# reefvolt_power_essentials_top.net
KiCad netlist of a schematic drawn in Altium Designer
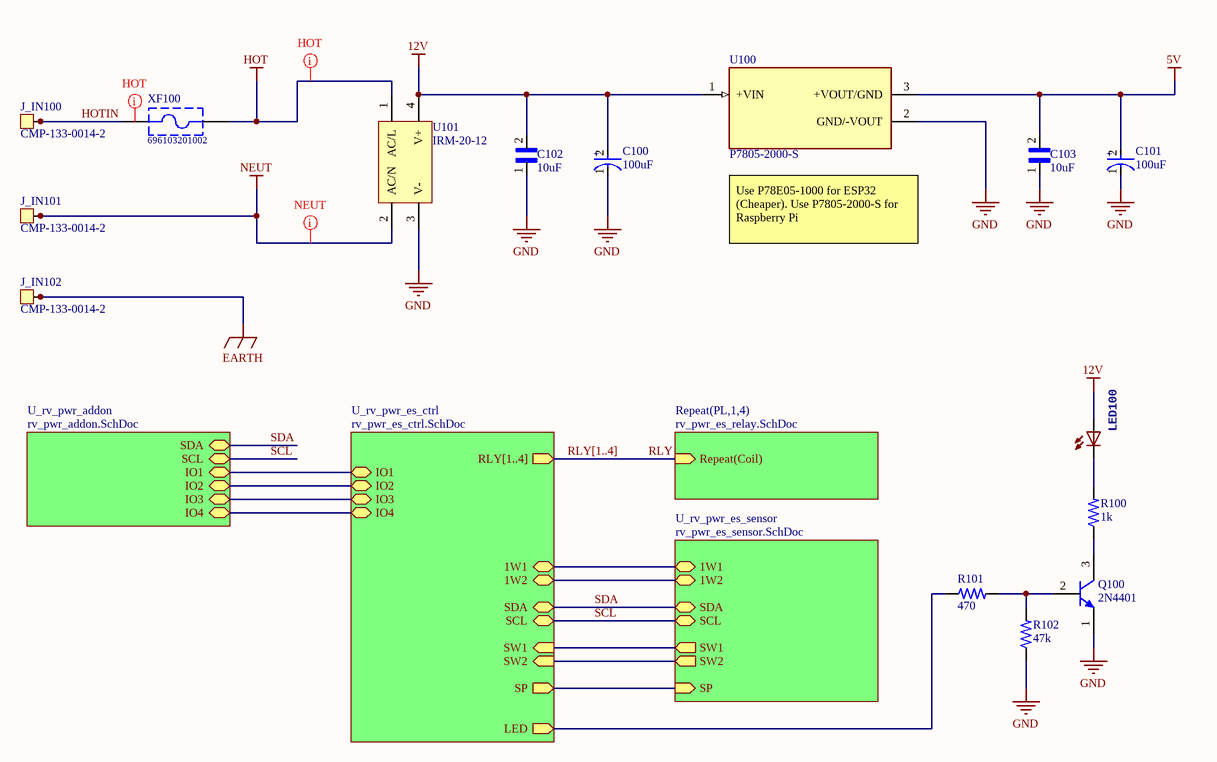
[diagram p0: reefvolt_power_essentials_top.SchDoc]

(export (version "E")
  (design (tool "Eeschema 10.0.6"))
  (components
    (comp (ref "C100")
      (value "100uF")
      (footprint "FP-RAD-TH-D_8_0_5-L_11_5-MFG")
      (description "Cap Aluminum 100uF 25V 20% (8 X 11.5mm) Radial 3.5mm 500mA 2000 hr 125°C Bulk")
      (fields (field (name "Comment") "CAP 100uF 25V Aluminum 8mm Through Hole"))
      (libsource (lib "StackFoundry LLC") (part "203bc49f2ac43e59fd269a8c329ed05"))
    )
    (comp (ref "C101")
      (value "100uF")
      (footprint "FP-RAD-TH-D_8_0_5-L_11_5-MFG")
      (description "Cap Aluminum 100uF 25V 20% (8 X 11.5mm) Radial 3.5mm 500mA 2000 hr 125°C Bulk")
      (fields (field (name "Comment") "CAP 100uF 25V Aluminum 8mm Through Hole"))
      (libsource (lib "StackFoundry LLC") (part "203bc49f2ac43e59fd269a8c329ed05"))
    )
    (comp (ref "C102")
      (value "10uF")
      (footprint "CAPRB250W50L550T350H600")
      (description "FG Series 10 uF 25 V ±10% Tolerance X7R Radial Multilayer Ceramic Capacitor")
      (fields (field (name "MF") "TDK") (field (name "DIGI-KEY_PART_NUMBER") "445-173156-1-ND"))
      (libsource (lib "StackFoundry LLC") (part "FG16X7R1E106KRT06"))
    )
    (comp (ref "C103")
      (value "10uF")
      (footprint "CAPRB250W50L550T350H600")
      (description "FG Series 10 uF 25 V ±10% Tolerance X7R Radial Multilayer Ceramic Capacitor")
      (fields (field (name "MF") "TDK") (field (name "DIGI-KEY_PART_NUMBER") "445-173156-1-ND"))
      (libsource (lib "StackFoundry LLC") (part "FG16X7R1E106KRT06"))
    )
    (comp (ref "J_IN100")
      (value "CMP-133-0014-2")
      (footprint "0197054203")
      (description "Molex  0197054203")
      (libsource (lib "StackFoundry LLC") (part "TAB_QUICKCON"))
    )
    (comp (ref "J_IN101")
      (value "CMP-133-0014-2")
      (footprint "0197054203")
      (description "Molex  0197054203")
      (libsource (lib "StackFoundry LLC") (part "TAB_QUICKCON"))
    )
    (comp (ref "J_IN102")
      (value "CMP-133-0014-2")
      (footprint "0197054203")
      (description "Molex  0197054203")
      (libsource (lib "StackFoundry LLC") (part "TAB_QUICKCON"))
    )
    (comp (ref "LED100") (value "~") (footprint "LED5MM") (libsource (lib "general") (part "LED5MM")))
    (comp (ref "Q100")
      (value "2N4401")
      (footprint "ONSC-TO-92-3-29-11")
      (description "Transistor NPN Silicon 40V IC=600ma TO-92 Case General Purpose Amplifier And Switch")
      (fields (field (name "MF") "Rectron"))
      (libsource (lib "StackFoundry LLC") (part "ONSC-NPN-E1B2C3-3"))
    )
    (comp (ref "R100")
      (value "1k")
      (footprint "0207/10")
      (description "Res Carbon Film 1K Ohm 5% 1/4W -500ppm/°C to 350ppm/°C Conformal AXL Thru-Hole Paper T/R")
      (fields (field (name "Comment") "1k TH 0207 5% 0.25W"))
      (libsource (lib "StackFoundry LLC") (part "R-US"))
    )
    (comp (ref "R101")
      (value "470")
      (footprint "0207/10")
      (description "Res Carbon Film 470 Ohm 5% 1/4W -500ppm/°C to 350ppm/°C Conformal AXL Thru-Hole Paper T/R")
      (fields (field (name "Comment") "470 TH 0207 5% 0.25W"))
      (libsource (lib "StackFoundry LLC") (part "R-US"))
    )
    (comp (ref "R102")
      (value "47k")
      (footprint "0207/10 - Cloned")
      (description "Res Carbon Film 47K Ohm 5% 1/4W -500ppm/°C to 350ppm/°C Conformal AXL Thru-Hole Paper T/R")
      (fields (field (name "Comment") "47k TH 0207 5% 1/4W"))
      (libsource (lib "StackFoundry LLC") (part "R-US"))
    )
    (comp (ref "U100")
      (value "P7805-2000-S")
      (footprint "CONV_P7805-2000")
      (description "Module DC-DC 24VIN 1-OUT 5V 2A 10W 3-Pin SIP Module Tube")
      (libsource (lib "StackFoundry LLC") (part "P7805-2000-S"))
    )
    (comp (ref "U101")
      (value "IRM-20-12")
      (footprint "MEANW-IRM-20-12")
      (description "Single Output Encapsulated Type, 12 V, 1.8 A, 21.6 W, -40 to 85 degC, 4-Pin THD, RoHS")
      (fields (field (name "MANUFACTURER") "Mean Well"))
      (libsource (lib "Altium Content Vault") (part "MEANW-IRM-20-12-4"))
    )
    (comp (ref "XF100")
      (value "696103201002")
      (footprint "696103201002")
      (description "WR-FSH Fuse Holder Blocks Fuse Holder Blocks Clip Cover for PCB - THR Version")
      (libsource (lib "StackFoundry LLC") (part "WE-FUSE-2"))
    )
  )
  (nets
    (net (code "7") (name "/HOTIN") (class "Default")
      (node (ref "J_IN100") (pin "1") (pinfunction "1_1") (pintype "passive"))
      (node (ref "J_IN100") (pin "2") (pinfunction "2_2") (pintype "passive"))
      (node (ref "J_IN100") (pin "3") (pinfunction "3_3") (pintype "passive"))
      (node (ref "XF100") (pin "1") (pinfunction "1_1") (pintype "passive"))
    )
    (net (code "12") (name "/LED") (class "Default")
      (node (ref "R101") (pin "1") (pinfunction "1_1") (pintype "passive"))
    )
    (net (code "20") (name "5V") (class "Default")
      (node (ref "C101") (pin "2") (pinfunction "A_2") (pintype "passive"))
      (node (ref "C103") (pin "2") (pinfunction "2_2") (pintype "passive"))
      (node (ref "U100") (pin "3") (pinfunction "+VOUT/GND_3") (pintype "power_in"))
    )
    (net (code "21") (name "12V") (class "Default")
      (node (ref "C100") (pin "2") (pinfunction "A_2") (pintype "passive"))
      (node (ref "C102") (pin "2") (pinfunction "2_2") (pintype "passive"))
      (node (ref "LED100") (pin "A") (pinfunction "A_A") (pintype "passive"))
      (node (ref "U100") (pin "1") (pinfunction "+VIN_1") (pintype "input"))
      (node (ref "U101") (pin "4") (pinfunction "V+_4") (pintype "power_in"))
    )
    (net (code "22") (name "EARTH") (class "Default")
      (node (ref "J_IN102") (pin "1") (pinfunction "1_1") (pintype "passive"))
      (node (ref "J_IN102") (pin "2") (pinfunction "2_2") (pintype "passive"))
      (node (ref "J_IN102") (pin "3") (pinfunction "3_3") (pintype "passive"))
    )
    (net (code "23") (name "GND") (class "Default")
      (node (ref "C100") (pin "1") (pinfunction "C_1") (pintype "passive"))
      (node (ref "C101") (pin "1") (pinfunction "C_1") (pintype "passive"))
      (node (ref "C102") (pin "1") (pinfunction "1_1") (pintype "passive"))
      (node (ref "C103") (pin "1") (pinfunction "1_1") (pintype "passive"))
      (node (ref "Q100") (pin "1") (pinfunction "E_1") (pintype "passive"))
      (node (ref "R102") (pin "1") (pinfunction "1_1") (pintype "passive"))
      (node (ref "U100") (pin "2") (pinfunction "GND/-VOUT_2") (pintype "power_in"))
      (node (ref "U101") (pin "3") (pinfunction "V-_3") (pintype "power_in"))
    )
    (net (code "24") (name "HOT") (class "Default")
      (node (ref "U101") (pin "1") (pinfunction "AC/L_1") (pintype "passive"))
      (node (ref "XF100") (pin "2") (pinfunction "2_2") (pintype "passive"))
    )
    (net (code "25") (name "NEUT") (class "Default")
      (node (ref "J_IN101") (pin "1") (pinfunction "1_1") (pintype "passive"))
      (node (ref "J_IN101") (pin "2") (pinfunction "2_2") (pintype "passive"))
      (node (ref "J_IN101") (pin "3") (pinfunction "3_3") (pintype "passive"))
      (node (ref "U101") (pin "2") (pinfunction "AC/N_2") (pintype "passive"))
    )
    (net (code "26") (name "Net-(LED100-C)") (class "Default")
      (node (ref "LED100") (pin "K") (pinfunction "C_K") (pintype "passive"))
      (node (ref "R100") (pin "2") (pinfunction "2_2") (pintype "passive"))
    )
    (net (code "27") (name "Net-(Q100-B)") (class "Default")
      (node (ref "Q100") (pin "2") (pinfunction "B_2") (pintype "passive"))
      (node (ref "R101") (pin "2") (pinfunction "2_2") (pintype "passive"))
      (node (ref "R102") (pin "2") (pinfunction "2_2") (pintype "passive"))
    )
    (net (code "28") (name "Net-(Q100-C)") (class "Default")
      (node (ref "Q100") (pin "3") (pinfunction "C_3") (pintype "passive"))
      (node (ref "R100") (pin "1") (pinfunction "1_1") (pintype "passive"))
    )
  )
)
